# defluxio.net
KiCad netlist of a schematic drawn in EAGLE
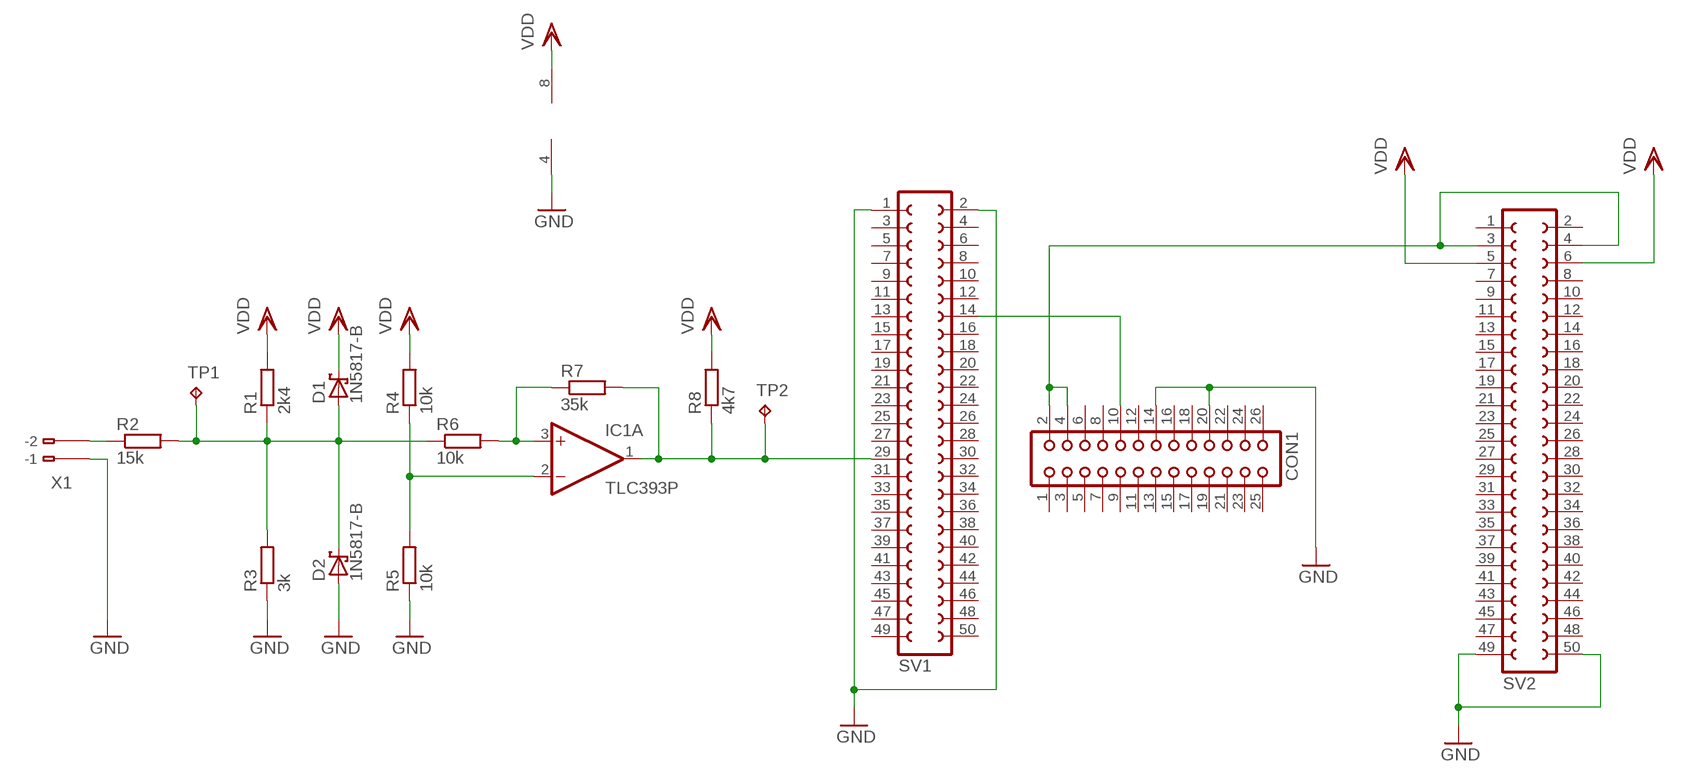
[diagram p0: schematic, sheet 1]

(export (version "E")
  (design (tool "Eeschema 10.0.6"))
  (components
    (comp (ref "CON1")
      (value "CON26")
      (footprint "eagle-import:CON26")
      (libsource (lib "eagle-import") (part "CON26"))
    )
    (comp (ref "D1")
      (value "1N5817-B")
      (footprint "eagle-import:DO41-7.6")
      (libsource (lib "eagle-import") (part "1N5817-B"))
    )
    (comp (ref "D2")
      (value "1N5817-B")
      (footprint "eagle-import:DO41-7.6")
      (libsource (lib "eagle-import") (part "1N5817-B"))
    )
    (comp (ref "IC1")
      (value "TLC393P")
      (footprint "eagle-import:DIL08")
      (libsource (lib "eagle-import") (part "TLC393P"))
    )
    (comp (ref "R1")
      (value "2k4")
      (footprint "eagle-import:0204_7")
      (libsource (lib "eagle-import") (part "R-EU_0204/7"))
    )
    (comp (ref "R2")
      (value "15k")
      (footprint "eagle-import:0207_12")
      (libsource (lib "eagle-import") (part "R-EU_0207/12"))
    )
    (comp (ref "R3")
      (value "3k")
      (footprint "eagle-import:0207_15")
      (libsource (lib "eagle-import") (part "R-EU_0207/15"))
    )
    (comp (ref "R4")
      (value "10k")
      (footprint "eagle-import:0207_12")
      (libsource (lib "eagle-import") (part "R-EU_0207/12"))
    )
    (comp (ref "R5")
      (value "10k")
      (footprint "eagle-import:0207_10")
      (libsource (lib "eagle-import") (part "R-EU_0207/10"))
    )
    (comp (ref "R6")
      (value "10k")
      (footprint "eagle-import:0204_7")
      (libsource (lib "eagle-import") (part "R-EU_0204/7"))
    )
    (comp (ref "R7")
      (value "35k")
      (footprint "eagle-import:0207_10")
      (libsource (lib "eagle-import") (part "R-EU_0207/10"))
    )
    (comp (ref "R8")
      (value "4k7")
      (footprint "eagle-import:0207_10")
      (libsource (lib "eagle-import") (part "R-EU_0207/10"))
    )
    (comp (ref "SV1")
      (value "FE25-2")
      (footprint "eagle-import:FE25-2")
      (libsource (lib "eagle-import") (part "FE25-2"))
    )
    (comp (ref "SV2")
      (value "FE25-2")
      (footprint "eagle-import:FE25-2")
      (libsource (lib "eagle-import") (part "FE25-2"))
    )
    (comp (ref "TP1")
      (value "TPPAD1-13")
      (footprint "eagle-import:P1-13")
      (libsource (lib "eagle-import") (part "TPPAD1-13"))
    )
    (comp (ref "TP2")
      (value "TPPAD1-13")
      (footprint "eagle-import:P1-13")
      (libsource (lib "eagle-import") (part "TPPAD1-13"))
    )
    (comp (ref "X1")
      (value "233-102")
      (footprint "eagle-import:233-102")
      (libsource (lib "eagle-import") (part "233-102"))
    )
  )
  (nets
    (net (code "1") (name "GND") (class "Default")
      (node (ref "CON1") (pin "14") (pinfunction "14_14") (pintype "passive"))
      (node (ref "CON1") (pin "20") (pinfunction "20_20") (pintype "passive"))
      (node (ref "D2") (pin "A") (pinfunction "A_A") (pintype "passive"))
      (node (ref "IC1") (pin "4") (pinfunction "V-_4") (pintype "power_in"))
      (node (ref "R3") (pin "1") (pinfunction "1_1") (pintype "passive"))
      (node (ref "R5") (pin "1") (pinfunction "1_1") (pintype "passive"))
      (node (ref "SV1") (pin "1") (pinfunction "1_1") (pintype "passive"))
      (node (ref "SV1") (pin "2") (pinfunction "2_2") (pintype "passive"))
      (node (ref "SV2") (pin "49") (pinfunction "49_49") (pintype "passive"))
      (node (ref "SV2") (pin "50") (pinfunction "50_50") (pintype "passive"))
      (node (ref "X1") (pin "B1") (pinfunction "B-1_B1") (pintype "passive"))
    )
    (net (code "2") (name "Net-(CON1-Pad2)") (class "Default")
      (node (ref "CON1") (pin "2") (pinfunction "2_2") (pintype "passive"))
      (node (ref "CON1") (pin "4") (pinfunction "4_4") (pintype "passive"))
      (node (ref "SV2") (pin "3") (pinfunction "3_3") (pintype "passive"))
      (node (ref "SV2") (pin "4") (pinfunction "4_4") (pintype "passive"))
    )
    (net (code "3") (name "Net-(CON1-Pad10)") (class "Default")
      (node (ref "CON1") (pin "10") (pinfunction "10_10") (pintype "passive"))
      (node (ref "SV1") (pin "14") (pinfunction "14_14") (pintype "passive"))
    )
    (net (code "4") (name "Net-(D1-PadA)") (class "Default")
      (node (ref "D1") (pin "A") (pinfunction "A_A") (pintype "passive"))
      (node (ref "D2") (pin "C") (pinfunction "C_C") (pintype "passive"))
      (node (ref "R1") (pin "1") (pinfunction "1_1") (pintype "passive"))
      (node (ref "R2") (pin "2") (pinfunction "2_2") (pintype "passive"))
      (node (ref "R3") (pin "2") (pinfunction "2_2") (pintype "passive"))
      (node (ref "R6") (pin "1") (pinfunction "1_1") (pintype "passive"))
      (node (ref "TP1") (pin "TP") (pinfunction "TP_TP") (pintype "input"))
    )
    (net (code "5") (name "Net-(IC1A-+IN)") (class "Default")
      (node (ref "IC1") (pin "3") (pinfunction "+IN_3") (pintype "input"))
      (node (ref "R6") (pin "2") (pinfunction "2_2") (pintype "passive"))
      (node (ref "R7") (pin "1") (pinfunction "1_1") (pintype "passive"))
    )
    (net (code "6") (name "Net-(IC1A--IN)") (class "Default")
      (node (ref "IC1") (pin "2") (pinfunction "-IN_2") (pintype "input"))
      (node (ref "R4") (pin "1") (pinfunction "1_1") (pintype "passive"))
      (node (ref "R5") (pin "2") (pinfunction "2_2") (pintype "passive"))
    )
    (net (code "7") (name "Net-(IC1A-OUT)") (class "Default")
      (node (ref "IC1") (pin "1") (pinfunction "OUT_1") (pintype "output"))
      (node (ref "R7") (pin "2") (pinfunction "2_2") (pintype "passive"))
      (node (ref "R8") (pin "1") (pinfunction "1_1") (pintype "passive"))
      (node (ref "SV1") (pin "29") (pinfunction "29_29") (pintype "passive"))
      (node (ref "TP2") (pin "TP") (pinfunction "TP_TP") (pintype "input"))
    )
    (net (code "8") (name "Net-(X1-B-2)") (class "Default")
      (node (ref "R2") (pin "1") (pinfunction "1_1") (pintype "passive"))
      (node (ref "X1") (pin "B2") (pinfunction "B-2_B2") (pintype "passive"))
    )
    (net (code "9") (name "VDD") (class "Default")
      (node (ref "D1") (pin "C") (pinfunction "C_C") (pintype "passive"))
      (node (ref "IC1") (pin "8") (pinfunction "V+_8") (pintype "power_in"))
      (node (ref "R1") (pin "2") (pinfunction "2_2") (pintype "passive"))
      (node (ref "R4") (pin "2") (pinfunction "2_2") (pintype "passive"))
      (node (ref "R8") (pin "2") (pinfunction "2_2") (pintype "passive"))
      (node (ref "SV2") (pin "5") (pinfunction "5_5") (pintype "passive"))
      (node (ref "SV2") (pin "6") (pinfunction "6_6") (pintype "passive"))
    )
    (net (code "10") (name "unconnected-(CON1-Pad1)") (class "Default")
      (node (ref "CON1") (pin "1") (pinfunction "1_1") (pintype "passive"))
    )
    (net (code "11") (name "unconnected-(CON1-Pad3)") (class "Default")
      (node (ref "CON1") (pin "3") (pinfunction "3_3") (pintype "passive"))
    )
    (net (code "12") (name "unconnected-(CON1-Pad5)") (class "Default")
      (node (ref "CON1") (pin "5") (pinfunction "5_5") (pintype "passive"))
    )
    (net (code "13") (name "unconnected-(CON1-Pad6)") (class "Default")
      (node (ref "CON1") (pin "6") (pinfunction "6_6") (pintype "passive"))
    )
    (net (code "14") (name "unconnected-(CON1-Pad7)") (class "Default")
      (node (ref "CON1") (pin "7") (pinfunction "7_7") (pintype "passive"))
    )
    (net (code "15") (name "unconnected-(CON1-Pad8)") (class "Default")
      (node (ref "CON1") (pin "8") (pinfunction "8_8") (pintype "passive"))
    )
    (net (code "16") (name "unconnected-(CON1-Pad9)") (class "Default")
      (node (ref "CON1") (pin "9") (pinfunction "9_9") (pintype "passive"))
    )
    (net (code "17") (name "unconnected-(CON1-Pad11)") (class "Default")
      (node (ref "CON1") (pin "11") (pinfunction "11_11") (pintype "passive"))
    )
    (net (code "18") (name "unconnected-(CON1-Pad12)") (class "Default")
      (node (ref "CON1") (pin "12") (pinfunction "12_12") (pintype "passive"))
    )
    (net (code "19") (name "unconnected-(CON1-Pad13)") (class "Default")
      (node (ref "CON1") (pin "13") (pinfunction "13_13") (pintype "passive"))
    )
    (net (code "20") (name "unconnected-(CON1-Pad15)") (class "Default")
      (node (ref "CON1") (pin "15") (pinfunction "15_15") (pintype "passive"))
    )
    (net (code "21") (name "unconnected-(CON1-Pad16)") (class "Default")
      (node (ref "CON1") (pin "16") (pinfunction "16_16") (pintype "passive"))
    )
    (net (code "22") (name "unconnected-(CON1-Pad17)") (class "Default")
      (node (ref "CON1") (pin "17") (pinfunction "17_17") (pintype "passive"))
    )
    (net (code "23") (name "unconnected-(CON1-Pad18)") (class "Default")
      (node (ref "CON1") (pin "18") (pinfunction "18_18") (pintype "passive"))
    )
    (net (code "24") (name "unconnected-(CON1-Pad19)") (class "Default")
      (node (ref "CON1") (pin "19") (pinfunction "19_19") (pintype "passive"))
    )
    (net (code "25") (name "unconnected-(CON1-Pad21)") (class "Default")
      (node (ref "CON1") (pin "21") (pinfunction "21_21") (pintype "passive"))
    )
    (net (code "26") (name "unconnected-(CON1-Pad22)") (class "Default")
      (node (ref "CON1") (pin "22") (pinfunction "22_22") (pintype "passive"))
    )
    (net (code "27") (name "unconnected-(CON1-Pad23)") (class "Default")
      (node (ref "CON1") (pin "23") (pinfunction "23_23") (pintype "passive"))
    )
    (net (code "28") (name "unconnected-(CON1-Pad24)") (class "Default")
      (node (ref "CON1") (pin "24") (pinfunction "24_24") (pintype "passive"))
    )
    (net (code "29") (name "unconnected-(CON1-Pad25)") (class "Default")
      (node (ref "CON1") (pin "25") (pinfunction "25_25") (pintype "passive"))
    )
    (net (code "30") (name "unconnected-(CON1-Pad26)") (class "Default")
      (node (ref "CON1") (pin "26") (pinfunction "26_26") (pintype "passive"))
    )
    (net (code "31") (name "unconnected-(SV1-Pad3)") (class "Default")
      (node (ref "SV1") (pin "3") (pinfunction "3_3") (pintype "passive"))
    )
    (net (code "32") (name "unconnected-(SV1-Pad4)") (class "Default")
      (node (ref "SV1") (pin "4") (pinfunction "4_4") (pintype "passive"))
    )
    (net (code "33") (name "unconnected-(SV1-Pad5)") (class "Default")
      (node (ref "SV1") (pin "5") (pinfunction "5_5") (pintype "passive"))
    )
    (net (code "34") (name "unconnected-(SV1-Pad6)") (class "Default")
      (node (ref "SV1") (pin "6") (pinfunction "6_6") (pintype "passive"))
    )
    (net (code "35") (name "unconnected-(SV1-Pad7)") (class "Default")
      (node (ref "SV1") (pin "7") (pinfunction "7_7") (pintype "passive"))
    )
    (net (code "36") (name "unconnected-(SV1-Pad8)") (class "Default")
      (node (ref "SV1") (pin "8") (pinfunction "8_8") (pintype "passive"))
    )
    (net (code "37") (name "unconnected-(SV1-Pad9)") (class "Default")
      (node (ref "SV1") (pin "9") (pinfunction "9_9") (pintype "passive"))
    )
    (net (code "38") (name "unconnected-(SV1-Pad10)") (class "Default")
      (node (ref "SV1") (pin "10") (pinfunction "10_10") (pintype "passive"))
    )
    (net (code "39") (name "unconnected-(SV1-Pad11)") (class "Default")
      (node (ref "SV1") (pin "11") (pinfunction "11_11") (pintype "passive"))
    )
    (net (code "40") (name "unconnected-(SV1-Pad12)") (class "Default")
      (node (ref "SV1") (pin "12") (pinfunction "12_12") (pintype "passive"))
    )
    (net (code "41") (name "unconnected-(SV1-Pad13)") (class "Default")
      (node (ref "SV1") (pin "13") (pinfunction "13_13") (pintype "passive"))
    )
    (net (code "42") (name "unconnected-(SV1-Pad15)") (class "Default")
      (node (ref "SV1") (pin "15") (pinfunction "15_15") (pintype "passive"))
    )
    (net (code "43") (name "unconnected-(SV1-Pad16)") (class "Default")
      (node (ref "SV1") (pin "16") (pinfunction "16_16") (pintype "passive"))
    )
    (net (code "44") (name "unconnected-(SV1-Pad17)") (class "Default")
      (node (ref "SV1") (pin "17") (pinfunction "17_17") (pintype "passive"))
    )
    (net (code "45") (name "unconnected-(SV1-Pad18)") (class "Default")
      (node (ref "SV1") (pin "18") (pinfunction "18_18") (pintype "passive"))
    )
    (net (code "46") (name "unconnected-(SV1-Pad19)") (class "Default")
      (node (ref "SV1") (pin "19") (pinfunction "19_19") (pintype "passive"))
    )
    (net (code "47") (name "unconnected-(SV1-Pad20)") (class "Default")
      (node (ref "SV1") (pin "20") (pinfunction "20_20") (pintype "passive"))
    )
    (net (code "48") (name "unconnected-(SV1-Pad21)") (class "Default")
      (node (ref "SV1") (pin "21") (pinfunction "21_21") (pintype "passive"))
    )
    (net (code "49") (name "unconnected-(SV1-Pad22)") (class "Default")
      (node (ref "SV1") (pin "22") (pinfunction "22_22") (pintype "passive"))
    )
    (net (code "50") (name "unconnected-(SV1-Pad23)") (class "Default")
      (node (ref "SV1") (pin "23") (pinfunction "23_23") (pintype "passive"))
    )
    (net (code "51") (name "unconnected-(SV1-Pad24)") (class "Default")
      (node (ref "SV1") (pin "24") (pinfunction "24_24") (pintype "passive"))
    )
    (net (code "52") (name "unconnected-(SV1-Pad25)") (class "Default")
      (node (ref "SV1") (pin "25") (pinfunction "25_25") (pintype "passive"))
    )
    (net (code "53") (name "unconnected-(SV1-Pad26)") (class "Default")
      (node (ref "SV1") (pin "26") (pinfunction "26_26") (pintype "passive"))
    )
    (net (code "54") (name "unconnected-(SV1-Pad27)") (class "Default")
      (node (ref "SV1") (pin "27") (pinfunction "27_27") (pintype "passive"))
    )
    (net (code "55") (name "unconnected-(SV1-Pad28)") (class "Default")
      (node (ref "SV1") (pin "28") (pinfunction "28_28") (pintype "passive"))
    )
    (net (code "56") (name "unconnected-(SV1-Pad30)") (class "Default")
      (node (ref "SV1") (pin "30") (pinfunction "30_30") (pintype "passive"))
    )
    (net (code "57") (name "unconnected-(SV1-Pad31)") (class "Default")
      (node (ref "SV1") (pin "31") (pinfunction "31_31") (pintype "passive"))
    )
    (net (code "58") (name "unconnected-(SV1-Pad32)") (class "Default")
      (node (ref "SV1") (pin "32") (pinfunction "32_32") (pintype "passive"))
    )
    (net (code "59") (name "unconnected-(SV1-Pad33)") (class "Default")
      (node (ref "SV1") (pin "33") (pinfunction "33_33") (pintype "passive"))
    )
    (net (code "60") (name "unconnected-(SV1-Pad34)") (class "Default")
      (node (ref "SV1") (pin "34") (pinfunction "34_34") (pintype "passive"))
    )
    (net (code "61") (name "unconnected-(SV1-Pad35)") (class "Default")
      (node (ref "SV1") (pin "35") (pinfunction "35_35") (pintype "passive"))
    )
    (net (code "62") (name "unconnected-(SV1-Pad36)") (class "Default")
      (node (ref "SV1") (pin "36") (pinfunction "36_36") (pintype "passive"))
    )
    (net (code "63") (name "unconnected-(SV1-Pad37)") (class "Default")
      (node (ref "SV1") (pin "37") (pinfunction "37_37") (pintype "passive"))
    )
    (net (code "64") (name "unconnected-(SV1-Pad38)") (class "Default")
      (node (ref "SV1") (pin "38") (pinfunction "38_38") (pintype "passive"))
    )
    (net (code "65") (name "unconnected-(SV1-Pad39)") (class "Default")
      (node (ref "SV1") (pin "39") (pinfunction "39_39") (pintype "passive"))
    )
    (net (code "66") (name "unconnected-(SV1-Pad40)") (class "Default")
      (node (ref "SV1") (pin "40") (pinfunction "40_40") (pintype "passive"))
    )
    (net (code "67") (name "unconnected-(SV1-Pad41)") (class "Default")
      (node (ref "SV1") (pin "41") (pinfunction "41_41") (pintype "passive"))
    )
    (net (code "68") (name "unconnected-(SV1-Pad42)") (class "Default")
      (node (ref "SV1") (pin "42") (pinfunction "42_42") (pintype "passive"))
    )
    (net (code "69") (name "unconnected-(SV1-Pad43)") (class "Default")
      (node (ref "SV1") (pin "43") (pinfunction "43_43") (pintype "passive"))
    )
    (net (code "70") (name "unconnected-(SV1-Pad44)") (class "Default")
      (node (ref "SV1") (pin "44") (pinfunction "44_44") (pintype "passive"))
    )
    (net (code "71") (name "unconnected-(SV1-Pad45)") (class "Default")
      (node (ref "SV1") (pin "45") (pinfunction "45_45") (pintype "passive"))
    )
    (net (code "72") (name "unconnected-(SV1-Pad46)") (class "Default")
      (node (ref "SV1") (pin "46") (pinfunction "46_46") (pintype "passive"))
    )
    (net (code "73") (name "unconnected-(SV1-Pad47)") (class "Default")
      (node (ref "SV1") (pin "47") (pinfunction "47_47") (pintype "passive"))
    )
    (net (code "74") (name "unconnected-(SV1-Pad48)") (class "Default")
      (node (ref "SV1") (pin "48") (pinfunction "48_48") (pintype "passive"))
    )
    (net (code "75") (name "unconnected-(SV1-Pad49)") (class "Default")
      (node (ref "SV1") (pin "49") (pinfunction "49_49") (pintype "passive"))
    )
    (net (code "76") (name "unconnected-(SV1-Pad50)") (class "Default")
      (node (ref "SV1") (pin "50") (pinfunction "50_50") (pintype "passive"))
    )
    (net (code "77") (name "unconnected-(SV2-Pad1)") (class "Default")
      (node (ref "SV2") (pin "1") (pinfunction "1_1") (pintype "passive"))
    )
    (net (code "78") (name "unconnected-(SV2-Pad2)") (class "Default")
      (node (ref "SV2") (pin "2") (pinfunction "2_2") (pintype "passive"))
    )
    (net (code "79") (name "unconnected-(SV2-Pad7)") (class "Default")
      (node (ref "SV2") (pin "7") (pinfunction "7_7") (pintype "passive"))
    )
    (net (code "80") (name "unconnected-(SV2-Pad8)") (class "Default")
      (node (ref "SV2") (pin "8") (pinfunction "8_8") (pintype "passive"))
    )
    (net (code "81") (name "unconnected-(SV2-Pad9)") (class "Default")
      (node (ref "SV2") (pin "9") (pinfunction "9_9") (pintype "passive"))
    )
    (net (code "82") (name "unconnected-(SV2-Pad10)") (class "Default")
      (node (ref "SV2") (pin "10") (pinfunction "10_10") (pintype "passive"))
    )
    (net (code "83") (name "unconnected-(SV2-Pad11)") (class "Default")
      (node (ref "SV2") (pin "11") (pinfunction "11_11") (pintype "passive"))
    )
    (net (code "84") (name "unconnected-(SV2-Pad12)") (class "Default")
      (node (ref "SV2") (pin "12") (pinfunction "12_12") (pintype "passive"))
    )
    (net (code "85") (name "unconnected-(SV2-Pad13)") (class "Default")
      (node (ref "SV2") (pin "13") (pinfunction "13_13") (pintype "passive"))
    )
    (net (code "86") (name "unconnected-(SV2-Pad14)") (class "Default")
      (node (ref "SV2") (pin "14") (pinfunction "14_14") (pintype "passive"))
    )
    (net (code "87") (name "unconnected-(SV2-Pad15)") (class "Default")
      (node (ref "SV2") (pin "15") (pinfunction "15_15") (pintype "passive"))
    )
    (net (code "88") (name "unconnected-(SV2-Pad16)") (class "Default")
      (node (ref "SV2") (pin "16") (pinfunction "16_16") (pintype "passive"))
    )
    (net (code "89") (name "unconnected-(SV2-Pad17)") (class "Default")
      (node (ref "SV2") (pin "17") (pinfunction "17_17") (pintype "passive"))
    )
    (net (code "90") (name "unconnected-(SV2-Pad18)") (class "Default")
      (node (ref "SV2") (pin "18") (pinfunction "18_18") (pintype "passive"))
    )
    (net (code "91") (name "unconnected-(SV2-Pad19)") (class "Default")
      (node (ref "SV2") (pin "19") (pinfunction "19_19") (pintype "passive"))
    )
    (net (code "92") (name "unconnected-(SV2-Pad20)") (class "Default")
      (node (ref "SV2") (pin "20") (pinfunction "20_20") (pintype "passive"))
    )
    (net (code "93") (name "unconnected-(SV2-Pad21)") (class "Default")
      (node (ref "SV2") (pin "21") (pinfunction "21_21") (pintype "passive"))
    )
    (net (code "94") (name "unconnected-(SV2-Pad22)") (class "Default")
      (node (ref "SV2") (pin "22") (pinfunction "22_22") (pintype "passive"))
    )
    (net (code "95") (name "unconnected-(SV2-Pad23)") (class "Default")
      (node (ref "SV2") (pin "23") (pinfunction "23_23") (pintype "passive"))
    )
    (net (code "96") (name "unconnected-(SV2-Pad24)") (class "Default")
      (node (ref "SV2") (pin "24") (pinfunction "24_24") (pintype "passive"))
    )
    (net (code "97") (name "unconnected-(SV2-Pad25)") (class "Default")
      (node (ref "SV2") (pin "25") (pinfunction "25_25") (pintype "passive"))
    )
    (net (code "98") (name "unconnected-(SV2-Pad26)") (class "Default")
      (node (ref "SV2") (pin "26") (pinfunction "26_26") (pintype "passive"))
    )
    (net (code "99") (name "unconnected-(SV2-Pad27)") (class "Default")
      (node (ref "SV2") (pin "27") (pinfunction "27_27") (pintype "passive"))
    )
    (net (code "100") (name "unconnected-(SV2-Pad28)") (class "Default")
      (node (ref "SV2") (pin "28") (pinfunction "28_28") (pintype "passive"))
    )
    (net (code "101") (name "unconnected-(SV2-Pad29)") (class "Default")
      (node (ref "SV2") (pin "29") (pinfunction "29_29") (pintype "passive"))
    )
    (net (code "102") (name "unconnected-(SV2-Pad30)") (class "Default")
      (node (ref "SV2") (pin "30") (pinfunction "30_30") (pintype "passive"))
    )
    (net (code "103") (name "unconnected-(SV2-Pad31)") (class "Default")
      (node (ref "SV2") (pin "31") (pinfunction "31_31") (pintype "passive"))
    )
    (net (code "104") (name "unconnected-(SV2-Pad32)") (class "Default")
      (node (ref "SV2") (pin "32") (pinfunction "32_32") (pintype "passive"))
    )
    (net (code "105") (name "unconnected-(SV2-Pad33)") (class "Default")
      (node (ref "SV2") (pin "33") (pinfunction "33_33") (pintype "passive"))
    )
    (net (code "106") (name "unconnected-(SV2-Pad34)") (class "Default")
      (node (ref "SV2") (pin "34") (pinfunction "34_34") (pintype "passive"))
    )
    (net (code "107") (name "unconnected-(SV2-Pad35)") (class "Default")
      (node (ref "SV2") (pin "35") (pinfunction "35_35") (pintype "passive"))
    )
    (net (code "108") (name "unconnected-(SV2-Pad36)") (class "Default")
      (node (ref "SV2") (pin "36") (pinfunction "36_36") (pintype "passive"))
    )
    (net (code "109") (name "unconnected-(SV2-Pad37)") (class "Default")
      (node (ref "SV2") (pin "37") (pinfunction "37_37") (pintype "passive"))
    )
    (net (code "110") (name "unconnected-(SV2-Pad38)") (class "Default")
      (node (ref "SV2") (pin "38") (pinfunction "38_38") (pintype "passive"))
    )
    (net (code "111") (name "unconnected-(SV2-Pad39)") (class "Default")
      (node (ref "SV2") (pin "39") (pinfunction "39_39") (pintype "passive"))
    )
    (net (code "112") (name "unconnected-(SV2-Pad40)") (class "Default")
      (node (ref "SV2") (pin "40") (pinfunction "40_40") (pintype "passive"))
    )
    (net (code "113") (name "unconnected-(SV2-Pad41)") (class "Default")
      (node (ref "SV2") (pin "41") (pinfunction "41_41") (pintype "passive"))
    )
    (net (code "114") (name "unconnected-(SV2-Pad42)") (class "Default")
      (node (ref "SV2") (pin "42") (pinfunction "42_42") (pintype "passive"))
    )
    (net (code "115") (name "unconnected-(SV2-Pad43)") (class "Default")
      (node (ref "SV2") (pin "43") (pinfunction "43_43") (pintype "passive"))
    )
    (net (code "116") (name "unconnected-(SV2-Pad44)") (class "Default")
      (node (ref "SV2") (pin "44") (pinfunction "44_44") (pintype "passive"))
    )
    (net (code "117") (name "unconnected-(SV2-Pad45)") (class "Default")
      (node (ref "SV2") (pin "45") (pinfunction "45_45") (pintype "passive"))
    )
    (net (code "118") (name "unconnected-(SV2-Pad46)") (class "Default")
      (node (ref "SV2") (pin "46") (pinfunction "46_46") (pintype "passive"))
    )
    (net (code "119") (name "unconnected-(SV2-Pad47)") (class "Default")
      (node (ref "SV2") (pin "47") (pinfunction "47_47") (pintype "passive"))
    )
    (net (code "120") (name "unconnected-(SV2-Pad48)") (class "Default")
      (node (ref "SV2") (pin "48") (pinfunction "48_48") (pintype "passive"))
    )
    (net (code "121") (name "unconnected-(X1--1-PadA1)") (class "Default")
      (node (ref "X1") (pin "A1") (pinfunction "-1_A1") (pintype "passive"))
    )
    (net (code "122") (name "unconnected-(X1--2-PadA2)") (class "Default")
      (node (ref "X1") (pin "A2") (pinfunction "-2_A2") (pintype "passive"))
    )
  )
)
